# uMotion_v1_0.net
KiCad netlist of a schematic drawn in EAGLE
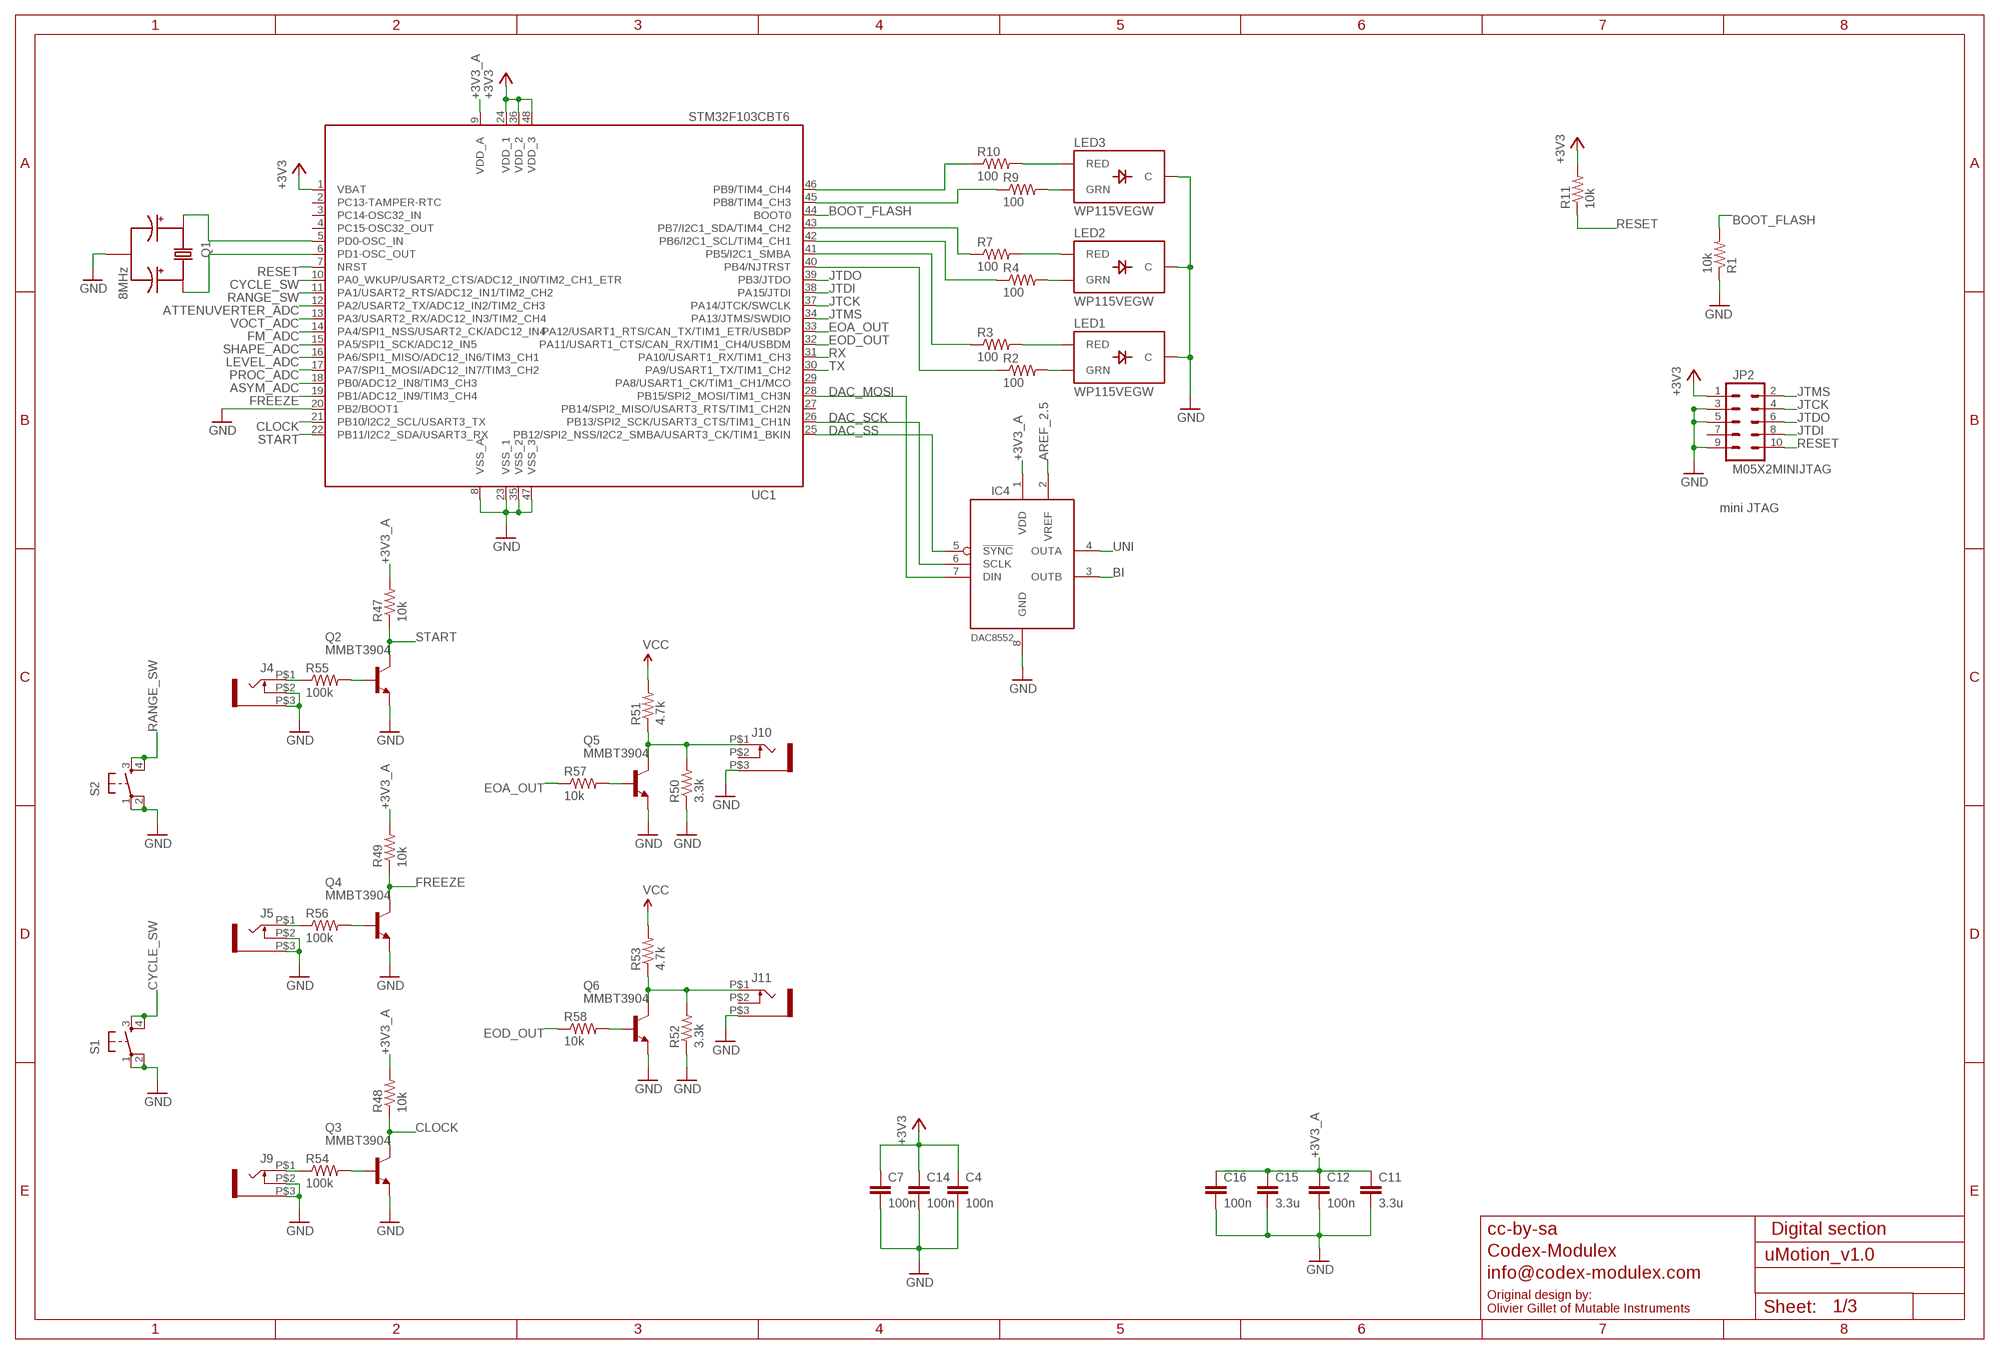
[diagram p0: schematic, sheet 1]
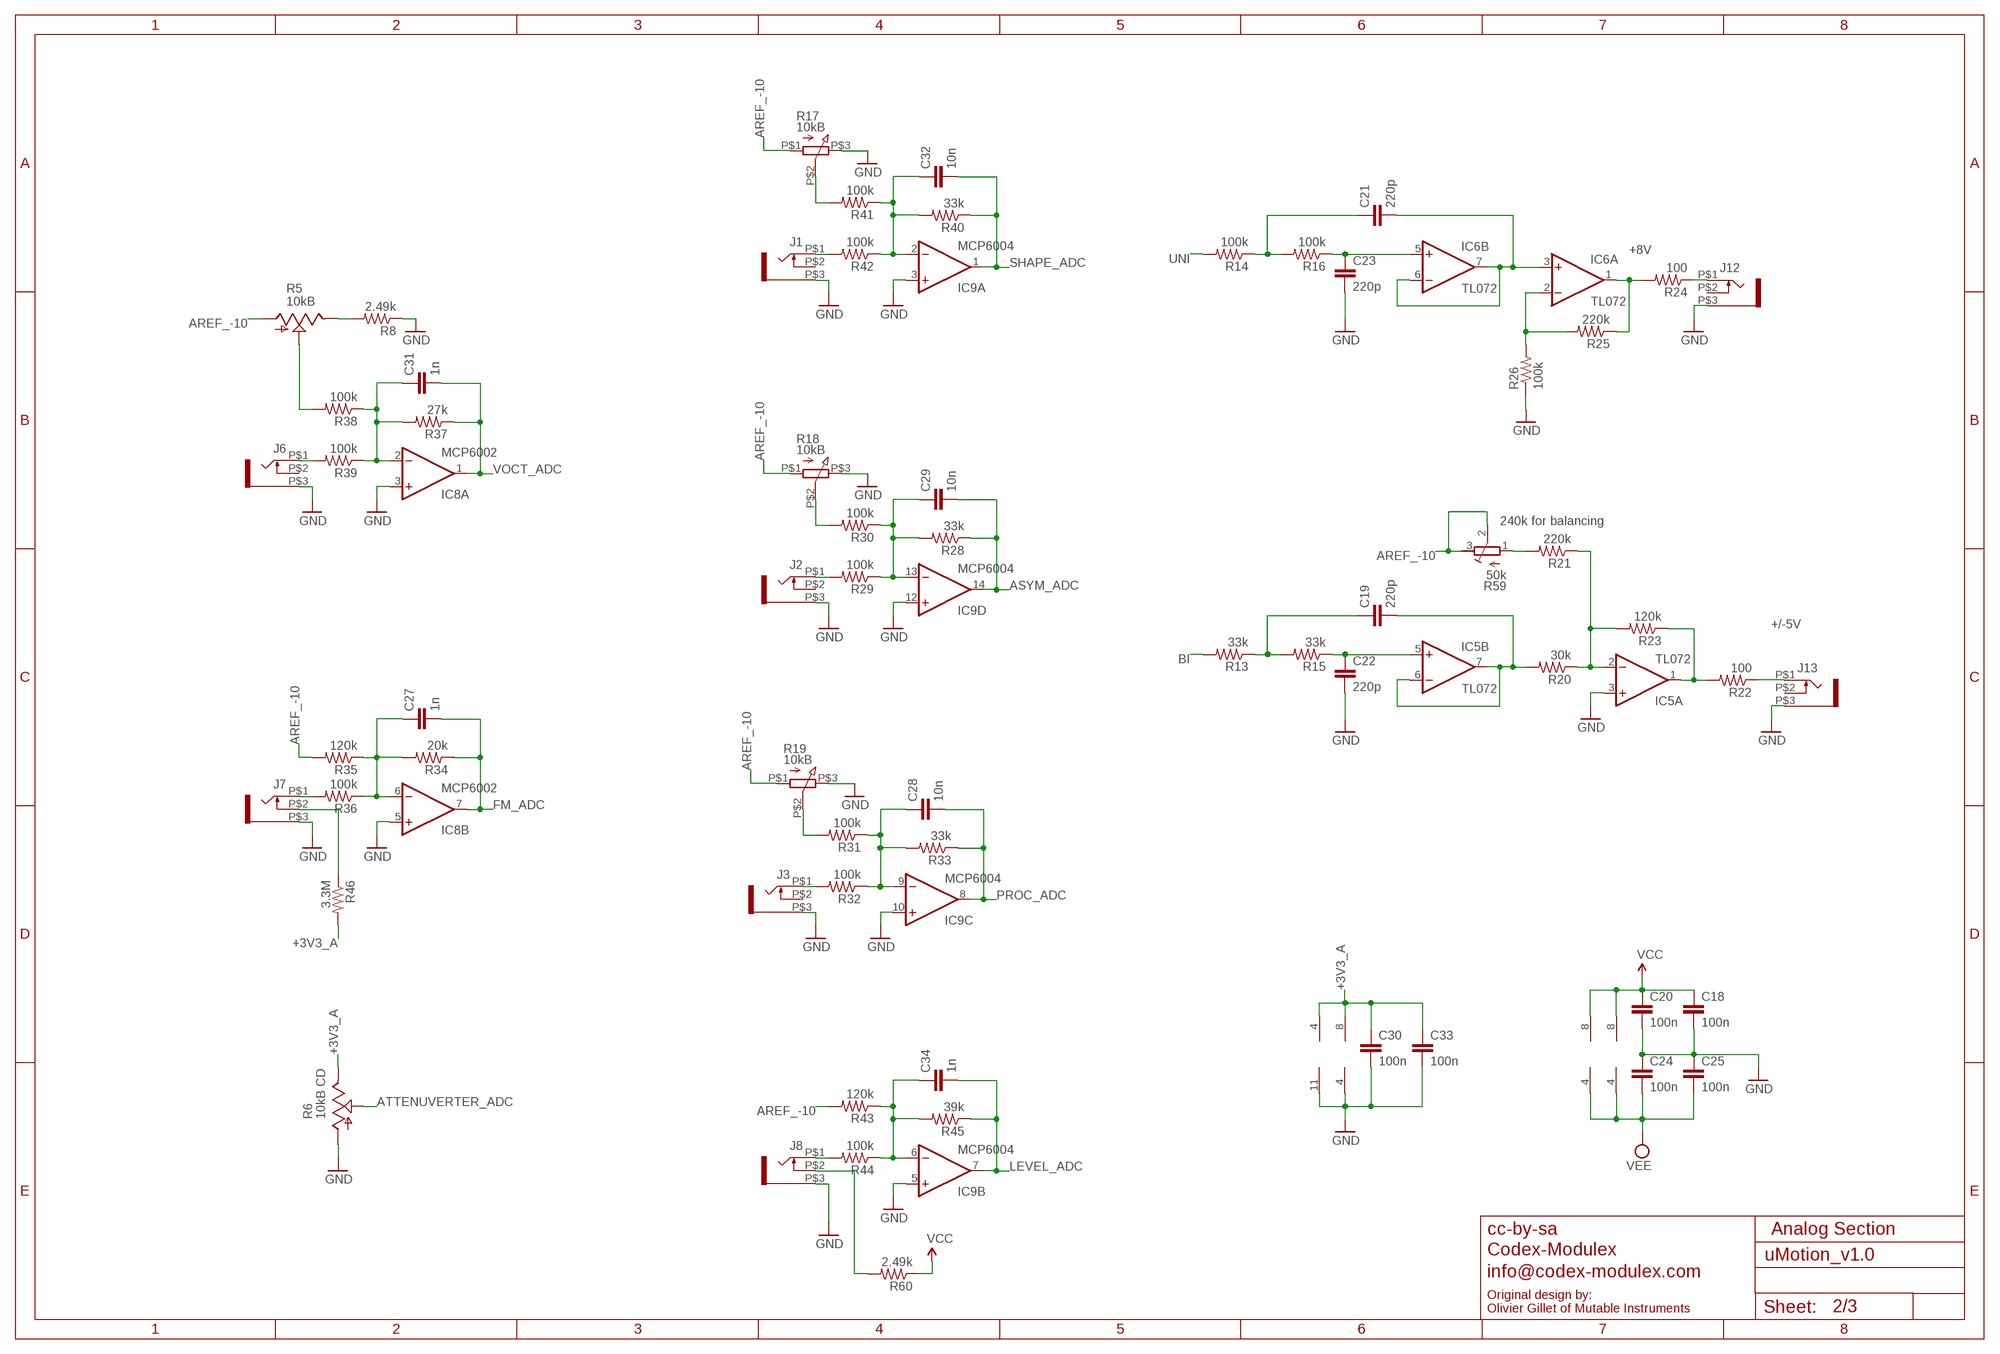
[diagram p1: schematic, sheet 2]
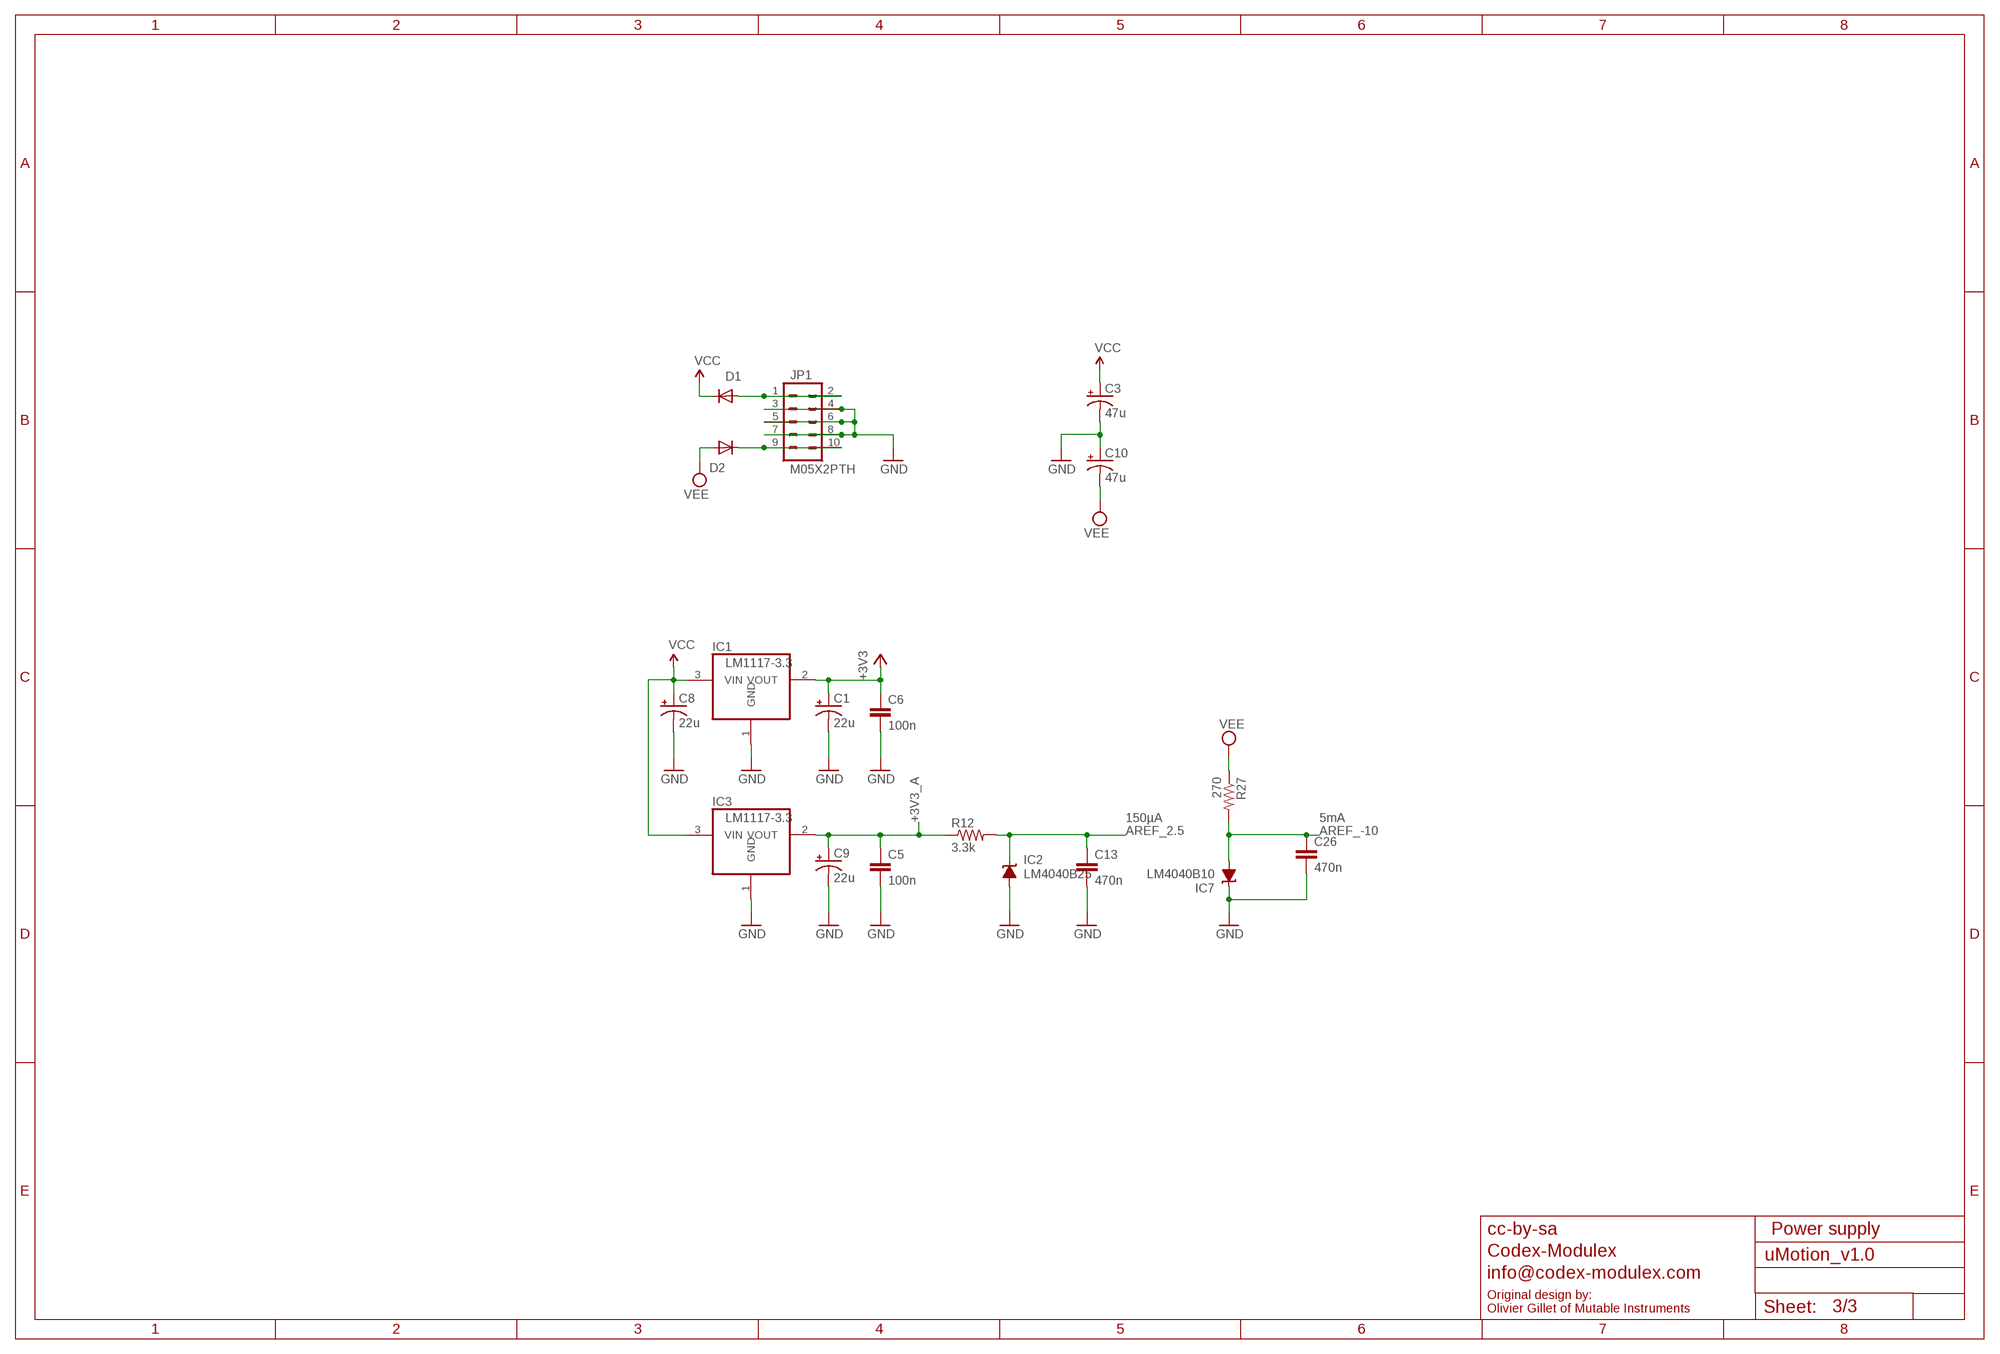
[diagram p2: schematic, sheet 3]

(export (version "E")
  (design (tool "Eeschema 10.0.6"))
  (components
    (comp (ref "C1")
      (value "22u")
      (footprint "eagle-import:PANASONIC_C")
      (libsource (lib "eagle-import") (part "CPOL-USC"))
    )
    (comp (ref "C3")
      (value "47u")
      (footprint "eagle-import:PANASONIC_D")
      (libsource (lib "eagle-import") (part "CPOL-USD"))
    )
    (comp (ref "C5")
      (value "100n")
      (footprint "eagle-import:PARTS_AMAN_RESISTOR_0603")
      (libsource (lib "eagle-import") (part "PARTS_AMAN_CAPACITOR"))
    )
    (comp (ref "C6")
      (value "100n")
      (footprint "eagle-import:PARTS_AMAN_RESISTOR_0603")
      (libsource (lib "eagle-import") (part "PARTS_AMAN_CAPACITOR"))
    )
    (comp (ref "C8")
      (value "22u")
      (footprint "eagle-import:PANASONIC_C")
      (libsource (lib "eagle-import") (part "CPOL-USC"))
    )
    (comp (ref "C9")
      (value "22u")
      (footprint "eagle-import:PANASONIC_C")
      (libsource (lib "eagle-import") (part "CPOL-USC"))
    )
    (comp (ref "C10")
      (value "47u")
      (footprint "eagle-import:PANASONIC_D")
      (libsource (lib "eagle-import") (part "CPOL-USD"))
    )
    (comp (ref "C13")
      (value "470n")
      (footprint "eagle-import:PARTS_AMAN_RESISTOR_0603")
      (libsource (lib "eagle-import") (part "PARTS_AMAN_CAPACITOR"))
    )
    (comp (ref "C26")
      (value "470n")
      (footprint "eagle-import:PARTS_AMAN_RESISTOR_0603")
      (libsource (lib "eagle-import") (part "PARTS_AMAN_CAPACITOR"))
    )
    (comp (ref "D1")
      (value "1N5819HW")
      (footprint "eagle-import:SOD123")
      (libsource (lib "eagle-import") (part "DIODE-SOD123"))
    )
    (comp (ref "D2")
      (value "1N5819HW")
      (footprint "eagle-import:SOD123")
      (libsource (lib "eagle-import") (part "DIODE-SOD123"))
    )
    (comp (ref "IC1")
      (value "LM1117-3.3")
      (footprint "eagle-import:SOT223")
      (libsource (lib "eagle-import") (part "REG1117"))
    )
    (comp (ref "IC2")
      (value "LM4040B25")
      (footprint "eagle-import:DBZ_R-PDSO-G3")
      (libsource (lib "eagle-import") (part "LM4041DBZB12"))
    )
    (comp (ref "IC3")
      (value "LM1117-3.3")
      (footprint "eagle-import:SOT223")
      (libsource (lib "eagle-import") (part "REG1117"))
    )
    (comp (ref "IC7")
      (value "LM4040B10")
      (footprint "eagle-import:DBZ_R-PDSO-G3")
      (libsource (lib "eagle-import") (part "LM4041DBZB12"))
    )
    (comp (ref "JP1")
      (value "M05X2PTH")
      (footprint "eagle-import:AVR_ICSP")
      (libsource (lib "eagle-import") (part "M05X2PTH"))
    )
    (comp (ref "R12")
      (value "3.3k")
      (footprint "eagle-import:PARTS_AMAN_RESISTOR_0603")
      (libsource (lib "eagle-import") (part "PARTS_AMAN_RESISTOR"))
    )
    (comp (ref "R27")
      (value "270")
      (footprint "eagle-import:PARTS_AMAN_RESISTOR_0603")
      (libsource (lib "eagle-import") (part "PARTS_AMAN_RESISTOR"))
    )
    (comp (ref "C18")
      (value "100n")
      (footprint "eagle-import:PARTS_AMAN_RESISTOR_0603")
      (libsource (lib "eagle-import") (part "PARTS_AMAN_CAPACITOR"))
    )
    (comp (ref "C19")
      (value "220p")
      (footprint "eagle-import:PARTS_AMAN_RESISTOR_0603")
      (libsource (lib "eagle-import") (part "PARTS_AMAN_CAPACITOR"))
    )
    (comp (ref "C20")
      (value "100n")
      (footprint "eagle-import:PARTS_AMAN_RESISTOR_0603")
      (libsource (lib "eagle-import") (part "PARTS_AMAN_CAPACITOR"))
    )
    (comp (ref "C21")
      (value "220p")
      (footprint "eagle-import:PARTS_AMAN_RESISTOR_0603")
      (libsource (lib "eagle-import") (part "PARTS_AMAN_CAPACITOR"))
    )
    (comp (ref "C22")
      (value "220p")
      (footprint "eagle-import:PARTS_AMAN_RESISTOR_0603")
      (libsource (lib "eagle-import") (part "PARTS_AMAN_CAPACITOR"))
    )
    (comp (ref "C23")
      (value "220p")
      (footprint "eagle-import:PARTS_AMAN_RESISTOR_0603")
      (libsource (lib "eagle-import") (part "PARTS_AMAN_CAPACITOR"))
    )
    (comp (ref "C24")
      (value "100n")
      (footprint "eagle-import:PARTS_AMAN_RESISTOR_0603")
      (libsource (lib "eagle-import") (part "PARTS_AMAN_CAPACITOR"))
    )
    (comp (ref "C25")
      (value "100n")
      (footprint "eagle-import:PARTS_AMAN_RESISTOR_0603")
      (libsource (lib "eagle-import") (part "PARTS_AMAN_CAPACITOR"))
    )
    (comp (ref "C27")
      (value "1n")
      (footprint "eagle-import:PARTS_AMAN_RESISTOR_0603")
      (libsource (lib "eagle-import") (part "PARTS_AMAN_CAPACITOR"))
    )
    (comp (ref "C28")
      (value "10n")
      (footprint "eagle-import:PARTS_AMAN_RESISTOR_0603")
      (libsource (lib "eagle-import") (part "PARTS_AMAN_CAPACITOR"))
    )
    (comp (ref "C29")
      (value "10n")
      (footprint "eagle-import:PARTS_AMAN_RESISTOR_0603")
      (libsource (lib "eagle-import") (part "PARTS_AMAN_CAPACITOR"))
    )
    (comp (ref "C30")
      (value "100n")
      (footprint "eagle-import:PARTS_AMAN_RESISTOR_0603")
      (libsource (lib "eagle-import") (part "PARTS_AMAN_CAPACITOR"))
    )
    (comp (ref "C31")
      (value "1n")
      (footprint "eagle-import:PARTS_AMAN_RESISTOR_0603")
      (libsource (lib "eagle-import") (part "PARTS_AMAN_CAPACITOR"))
    )
    (comp (ref "C32")
      (value "10n")
      (footprint "eagle-import:PARTS_AMAN_RESISTOR_0603")
      (libsource (lib "eagle-import") (part "PARTS_AMAN_CAPACITOR"))
    )
    (comp (ref "C33")
      (value "100n")
      (footprint "eagle-import:PARTS_AMAN_RESISTOR_0603")
      (libsource (lib "eagle-import") (part "PARTS_AMAN_CAPACITOR"))
    )
    (comp (ref "C34")
      (value "1n")
      (footprint "eagle-import:PARTS_AMAN_RESISTOR_0603")
      (libsource (lib "eagle-import") (part "PARTS_AMAN_CAPACITOR"))
    )
    (comp (ref "IC5")
      (value "TL072")
      (footprint "eagle-import:SO08")
      (libsource (lib "eagle-import") (part "TL072D"))
    )
    (comp (ref "IC6")
      (value "TL072")
      (footprint "eagle-import:SO08")
      (libsource (lib "eagle-import") (part "TL072D"))
    )
    (comp (ref "IC8")
      (value "MCP6002")
      (footprint "eagle-import:SO08")
      (libsource (lib "eagle-import") (part "TL072D"))
    )
    (comp (ref "IC9")
      (value "MCP6004")
      (footprint "eagle-import:SO14")
      (libsource (lib "eagle-import") (part "TL074D"))
    )
    (comp (ref "J1")
      (value "WQP-PJ301M-12_JACK")
      (footprint "eagle-import:WQP-PJ301M-12_JACK")
      (libsource (lib "eagle-import") (part "WQP-PJ301M-12_JACK"))
    )
    (comp (ref "J2")
      (value "WQP-PJ301M-12_JACK")
      (footprint "eagle-import:WQP-PJ301M-12_JACK")
      (libsource (lib "eagle-import") (part "WQP-PJ301M-12_JACK"))
    )
    (comp (ref "J3")
      (value "WQP-PJ301M-12_JACK")
      (footprint "eagle-import:WQP-PJ301M-12_JACK")
      (libsource (lib "eagle-import") (part "WQP-PJ301M-12_JACK"))
    )
    (comp (ref "J6")
      (value "WQP-PJ301M-12_JACK")
      (footprint "eagle-import:WQP-PJ301M-12_JACK")
      (libsource (lib "eagle-import") (part "WQP-PJ301M-12_JACK"))
    )
    (comp (ref "J7")
      (value "WQP-PJ301M-12_JACK")
      (footprint "eagle-import:WQP-PJ301M-12_JACK")
      (libsource (lib "eagle-import") (part "WQP-PJ301M-12_JACK"))
    )
    (comp (ref "J8")
      (value "WQP-PJ301M-12_JACK")
      (footprint "eagle-import:WQP-PJ301M-12_JACK")
      (libsource (lib "eagle-import") (part "WQP-PJ301M-12_JACK"))
    )
    (comp (ref "J12")
      (value "WQP-PJ301M-12_JACK")
      (footprint "eagle-import:WQP-PJ301M-12_JACK")
      (libsource (lib "eagle-import") (part "WQP-PJ301M-12_JACK"))
    )
    (comp (ref "J13")
      (value "WQP-PJ301M-12_JACK")
      (footprint "eagle-import:WQP-PJ301M-12_JACK")
      (libsource (lib "eagle-import") (part "WQP-PJ301M-12_JACK"))
    )
    (comp (ref "R5")
      (value "10kB")
      (footprint "eagle-import:ALPS_POT_VERTICAL_PS")
      (libsource (lib "eagle-import") (part "POT_USVERTICAL_PS"))
    )
    (comp (ref "R6")
      (value "10kB CD")
      (footprint "eagle-import:ALPS_POT_VERTICAL_PS")
      (libsource (lib "eagle-import") (part "POT_USVERTICAL_PS"))
    )
    (comp (ref "R8")
      (value "2.49k")
      (footprint "eagle-import:PARTS_AMAN_RESISTOR_0603")
      (libsource (lib "eagle-import") (part "PARTS_AMAN_RESISTOR"))
    )
    (comp (ref "R13")
      (value "33k")
      (footprint "eagle-import:PARTS_AMAN_RESISTOR_0603")
      (libsource (lib "eagle-import") (part "PARTS_AMAN_RESISTOR"))
    )
    (comp (ref "R14")
      (value "100k")
      (footprint "eagle-import:PARTS_AMAN_RESISTOR_0603")
      (libsource (lib "eagle-import") (part "PARTS_AMAN_RESISTOR"))
    )
    (comp (ref "R15")
      (value "33k")
      (footprint "eagle-import:PARTS_AMAN_RESISTOR_0603")
      (libsource (lib "eagle-import") (part "PARTS_AMAN_RESISTOR"))
    )
    (comp (ref "R16")
      (value "100k")
      (footprint "eagle-import:PARTS_AMAN_RESISTOR_0603")
      (libsource (lib "eagle-import") (part "PARTS_AMAN_RESISTOR"))
    )
    (comp (ref "R17")
      (value "10kB")
      (footprint "eagle-import:INSTRUO_Q-POT2")
      (libsource (lib "eagle-import") (part "INSTRUO_Q-POT2"))
    )
    (comp (ref "R18")
      (value "10kB")
      (footprint "eagle-import:INSTRUO_Q-POT2")
      (libsource (lib "eagle-import") (part "INSTRUO_Q-POT2"))
    )
    (comp (ref "R19")
      (value "10kB")
      (footprint "eagle-import:INSTRUO_Q-POT2")
      (libsource (lib "eagle-import") (part "INSTRUO_Q-POT2"))
    )
    (comp (ref "R20")
      (value "30k")
      (footprint "eagle-import:PARTS_AMAN_RESISTOR_0603")
      (libsource (lib "eagle-import") (part "PARTS_AMAN_RESISTOR"))
    )
    (comp (ref "R21")
      (value "220k")
      (footprint "eagle-import:PARTS_AMAN_RESISTOR_0603")
      (libsource (lib "eagle-import") (part "PARTS_AMAN_RESISTOR"))
    )
    (comp (ref "R22")
      (value "100")
      (footprint "eagle-import:PARTS_AMAN_RESISTOR_0603")
      (libsource (lib "eagle-import") (part "PARTS_AMAN_RESISTOR"))
    )
    (comp (ref "R23")
      (value "120k")
      (footprint "eagle-import:PARTS_AMAN_RESISTOR_0603")
      (libsource (lib "eagle-import") (part "PARTS_AMAN_RESISTOR"))
    )
    (comp (ref "R24")
      (value "100")
      (footprint "eagle-import:PARTS_AMAN_RESISTOR_0603")
      (libsource (lib "eagle-import") (part "PARTS_AMAN_RESISTOR"))
    )
    (comp (ref "R25")
      (value "220k")
      (footprint "eagle-import:PARTS_AMAN_RESISTOR_0603")
      (libsource (lib "eagle-import") (part "PARTS_AMAN_RESISTOR"))
    )
    (comp (ref "R26")
      (value "100k")
      (footprint "eagle-import:PARTS_AMAN_RESISTOR_0603")
      (libsource (lib "eagle-import") (part "PARTS_AMAN_RESISTOR"))
    )
    (comp (ref "R28")
      (value "33k")
      (footprint "eagle-import:PARTS_AMAN_RESISTOR_0603")
      (libsource (lib "eagle-import") (part "PARTS_AMAN_RESISTOR"))
    )
    (comp (ref "R29")
      (value "100k")
      (footprint "eagle-import:PARTS_AMAN_RESISTOR_0603")
      (libsource (lib "eagle-import") (part "PARTS_AMAN_RESISTOR"))
    )
    (comp (ref "R30")
      (value "100k")
      (footprint "eagle-import:PARTS_AMAN_RESISTOR_0603")
      (libsource (lib "eagle-import") (part "PARTS_AMAN_RESISTOR"))
    )
    (comp (ref "R31")
      (value "100k")
      (footprint "eagle-import:PARTS_AMAN_RESISTOR_0603")
      (libsource (lib "eagle-import") (part "PARTS_AMAN_RESISTOR"))
    )
    (comp (ref "R32")
      (value "100k")
      (footprint "eagle-import:PARTS_AMAN_RESISTOR_0603")
      (libsource (lib "eagle-import") (part "PARTS_AMAN_RESISTOR"))
    )
    (comp (ref "R33")
      (value "33k")
      (footprint "eagle-import:PARTS_AMAN_RESISTOR_0603")
      (libsource (lib "eagle-import") (part "PARTS_AMAN_RESISTOR"))
    )
    (comp (ref "R34")
      (value "20k")
      (footprint "eagle-import:PARTS_AMAN_RESISTOR_0603")
      (libsource (lib "eagle-import") (part "PARTS_AMAN_RESISTOR"))
    )
    (comp (ref "R35")
      (value "120k")
      (footprint "eagle-import:PARTS_AMAN_RESISTOR_0603")
      (libsource (lib "eagle-import") (part "PARTS_AMAN_RESISTOR"))
    )
    (comp (ref "R36")
      (value "100k")
      (footprint "eagle-import:PARTS_AMAN_RESISTOR_0603")
      (libsource (lib "eagle-import") (part "PARTS_AMAN_RESISTOR"))
    )
    (comp (ref "R37")
      (value "27k")
      (footprint "eagle-import:PARTS_AMAN_RESISTOR_0603")
      (libsource (lib "eagle-import") (part "PARTS_AMAN_RESISTOR"))
    )
    (comp (ref "R38")
      (value "100k")
      (footprint "eagle-import:PARTS_AMAN_RESISTOR_0603")
      (libsource (lib "eagle-import") (part "PARTS_AMAN_RESISTOR"))
    )
    (comp (ref "R39")
      (value "100k")
      (footprint "eagle-import:PARTS_AMAN_RESISTOR_0603")
      (libsource (lib "eagle-import") (part "PARTS_AMAN_RESISTOR"))
    )
    (comp (ref "R40")
      (value "33k")
      (footprint "eagle-import:PARTS_AMAN_RESISTOR_0603")
      (libsource (lib "eagle-import") (part "PARTS_AMAN_RESISTOR"))
    )
    (comp (ref "R41")
      (value "100k")
      (footprint "eagle-import:PARTS_AMAN_RESISTOR_0603")
      (libsource (lib "eagle-import") (part "PARTS_AMAN_RESISTOR"))
    )
    (comp (ref "R42")
      (value "100k")
      (footprint "eagle-import:PARTS_AMAN_RESISTOR_0603")
      (libsource (lib "eagle-import") (part "PARTS_AMAN_RESISTOR"))
    )
    (comp (ref "R43")
      (value "120k")
      (footprint "eagle-import:PARTS_AMAN_RESISTOR_0603")
      (libsource (lib "eagle-import") (part "PARTS_AMAN_RESISTOR"))
    )
    (comp (ref "R44")
      (value "100k")
      (footprint "eagle-import:PARTS_AMAN_RESISTOR_0603")
      (libsource (lib "eagle-import") (part "PARTS_AMAN_RESISTOR"))
    )
    (comp (ref "R45")
      (value "39k")
      (footprint "eagle-import:PARTS_AMAN_RESISTOR_0603")
      (libsource (lib "eagle-import") (part "PARTS_AMAN_RESISTOR"))
    )
    (comp (ref "R46")
      (value "3.3M")
      (footprint "eagle-import:PARTS_AMAN_RESISTOR_0603")
      (libsource (lib "eagle-import") (part "PARTS_AMAN_RESISTOR"))
    )
    (comp (ref "R59")
      (value "50k")
      (footprint "eagle-import:RTRIM3296X")
      (libsource (lib "eagle-import") (part "R-TRIMM3296X"))
    )
    (comp (ref "R60")
      (value "2.49k")
      (footprint "eagle-import:R0805")
      (libsource (lib "eagle-import") (part "R-US_R0805"))
    )
    (comp (ref "C4")
      (value "100n")
      (footprint "eagle-import:PARTS_AMAN_RESISTOR_0603")
      (libsource (lib "eagle-import") (part "PARTS_AMAN_CAPACITOR"))
    )
    (comp (ref "C7")
      (value "100n")
      (footprint "eagle-import:PARTS_AMAN_RESISTOR_0603")
      (libsource (lib "eagle-import") (part "PARTS_AMAN_CAPACITOR"))
    )
    (comp (ref "C11")
      (value "3.3u")
      (footprint "eagle-import:PARTS_AMAN_RESISTOR_0603")
      (libsource (lib "eagle-import") (part "PARTS_AMAN_CAPACITOR"))
    )
    (comp (ref "C12")
      (value "100n")
      (footprint "eagle-import:PARTS_AMAN_RESISTOR_0603")
      (libsource (lib "eagle-import") (part "PARTS_AMAN_CAPACITOR"))
    )
    (comp (ref "C14")
      (value "100n")
      (footprint "eagle-import:PARTS_AMAN_RESISTOR_0603")
      (libsource (lib "eagle-import") (part "PARTS_AMAN_CAPACITOR"))
    )
    (comp (ref "C15")
      (value "3.3u")
      (footprint "eagle-import:PARTS_AMAN_RESISTOR_0603")
      (libsource (lib "eagle-import") (part "PARTS_AMAN_CAPACITOR"))
    )
    (comp (ref "C16")
      (value "100n")
      (footprint "eagle-import:PARTS_AMAN_RESISTOR_0603")
      (libsource (lib "eagle-import") (part "PARTS_AMAN_CAPACITOR"))
    )
    (comp (ref "IC4")
      (value "DAC8552")
      (footprint "eagle-import:MSOP-8")
      (libsource (lib "eagle-import") (part "DAC8552"))
    )
    (comp (ref "J4")
      (value "WQP-PJ301M-12_JACK")
      (footprint "eagle-import:WQP-PJ301M-12_JACK")
      (libsource (lib "eagle-import") (part "WQP-PJ301M-12_JACK"))
    )
    (comp (ref "J5")
      (value "WQP-PJ301M-12_JACK")
      (footprint "eagle-import:WQP-PJ301M-12_JACK")
      (libsource (lib "eagle-import") (part "WQP-PJ301M-12_JACK"))
    )
    (comp (ref "J9")
      (value "WQP-PJ301M-12_JACK")
      (footprint "eagle-import:WQP-PJ301M-12_JACK")
      (libsource (lib "eagle-import") (part "WQP-PJ301M-12_JACK"))
    )
    (comp (ref "J10")
      (value "WQP-PJ301M-12_JACK")
      (footprint "eagle-import:WQP-PJ301M-12_JACK")
      (libsource (lib "eagle-import") (part "WQP-PJ301M-12_JACK"))
    )
    (comp (ref "J11")
      (value "WQP-PJ301M-12_JACK")
      (footprint "eagle-import:WQP-PJ301M-12_JACK")
      (libsource (lib "eagle-import") (part "WQP-PJ301M-12_JACK"))
    )
    (comp (ref "JP2")
      (value "M05X2MINIJTAG")
      (footprint "eagle-import:2X5-1.27")
      (libsource (lib "eagle-import") (part "M05X2MINIJTAG"))
    )
    (comp (ref "LED1")
      (value "WP115VEGW")
      (footprint "eagle-import:LED-BICOLOR-THROUGHHOLE")
      (libsource (lib "eagle-import") (part "LED-BICOLOR-THROUGHHOLE"))
    )
    (comp (ref "LED2")
      (value "WP115VEGW")
      (footprint "eagle-import:LED-BICOLOR-THROUGHHOLE")
      (libsource (lib "eagle-import") (part "LED-BICOLOR-THROUGHHOLE"))
    )
    (comp (ref "LED3")
      (value "WP115VEGW")
      (footprint "eagle-import:LED-BICOLOR-THROUGHHOLE")
      (libsource (lib "eagle-import") (part "LED-BICOLOR-THROUGHHOLE"))
    )
    (comp (ref "Q1")
      (value "8MHz")
      (footprint "eagle-import:INSTRUO_CRYSTAL_SMALLER")
      (libsource (lib "eagle-import") (part "INSTRUO_CRYSTAL_SMALLER"))
    )
    (comp (ref "Q2")
      (value "MMBT3904")
      (footprint "eagle-import:SOT23-BEC")
      (libsource (lib "eagle-import") (part "-NPN-SOT23-BECMMBT3904LT1"))
    )
    (comp (ref "Q3")
      (value "MMBT3904")
      (footprint "eagle-import:SOT23-BEC")
      (libsource (lib "eagle-import") (part "-NPN-SOT23-BECMMBT3904LT1"))
    )
    (comp (ref "Q4")
      (value "MMBT3904")
      (footprint "eagle-import:SOT23-BEC")
      (libsource (lib "eagle-import") (part "-NPN-SOT23-BECMMBT3904LT1"))
    )
    (comp (ref "Q5")
      (value "MMBT3904")
      (footprint "eagle-import:SOT23-BEC")
      (libsource (lib "eagle-import") (part "-NPN-SOT23-BECMMBT3904LT1"))
    )
    (comp (ref "Q6")
      (value "MMBT3904")
      (footprint "eagle-import:SOT23-BEC")
      (libsource (lib "eagle-import") (part "-NPN-SOT23-BECMMBT3904LT1"))
    )
    (comp (ref "R1")
      (value "10k")
      (footprint "eagle-import:PARTS_AMAN_RESISTOR_0603")
      (libsource (lib "eagle-import") (part "PARTS_AMAN_RESISTOR"))
    )
    (comp (ref "R2")
      (value "100")
      (footprint "eagle-import:PARTS_AMAN_RESISTOR_0603")
      (libsource (lib "eagle-import") (part "PARTS_AMAN_RESISTOR"))
    )
    (comp (ref "R3")
      (value "100")
      (footprint "eagle-import:PARTS_AMAN_RESISTOR_0603")
      (libsource (lib "eagle-import") (part "PARTS_AMAN_RESISTOR"))
    )
    (comp (ref "R4")
      (value "100")
      (footprint "eagle-import:PARTS_AMAN_RESISTOR_0603")
      (libsource (lib "eagle-import") (part "PARTS_AMAN_RESISTOR"))
    )
    (comp (ref "R7")
      (value "100")
      (footprint "eagle-import:PARTS_AMAN_RESISTOR_0603")
      (libsource (lib "eagle-import") (part "PARTS_AMAN_RESISTOR"))
    )
    (comp (ref "R9")
      (value "100")
      (footprint "eagle-import:PARTS_AMAN_RESISTOR_0603")
      (libsource (lib "eagle-import") (part "PARTS_AMAN_RESISTOR"))
    )
    (comp (ref "R10")
      (value "100")
      (footprint "eagle-import:PARTS_AMAN_RESISTOR_0603")
      (libsource (lib "eagle-import") (part "PARTS_AMAN_RESISTOR"))
    )
    (comp (ref "R11")
      (value "10k")
      (footprint "eagle-import:PARTS_AMAN_RESISTOR_0603")
      (libsource (lib "eagle-import") (part "PARTS_AMAN_RESISTOR"))
    )
    (comp (ref "R47")
      (value "10k")
      (footprint "eagle-import:PARTS_AMAN_RESISTOR_0603")
      (libsource (lib "eagle-import") (part "PARTS_AMAN_RESISTOR"))
    )
    (comp (ref "R48")
      (value "10k")
      (footprint "eagle-import:PARTS_AMAN_RESISTOR_0603")
      (libsource (lib "eagle-import") (part "PARTS_AMAN_RESISTOR"))
    )
    (comp (ref "R49")
      (value "10k")
      (footprint "eagle-import:PARTS_AMAN_RESISTOR_0603")
      (libsource (lib "eagle-import") (part "PARTS_AMAN_RESISTOR"))
    )
    (comp (ref "R50")
      (value "3.3k")
      (footprint "eagle-import:PARTS_AMAN_RESISTOR_0603")
      (libsource (lib "eagle-import") (part "PARTS_AMAN_RESISTOR"))
    )
    (comp (ref "R51")
      (value "4.7k")
      (footprint "eagle-import:PARTS_AMAN_RESISTOR_0603")
      (libsource (lib "eagle-import") (part "PARTS_AMAN_RESISTOR"))
    )
    (comp (ref "R52")
      (value "3.3k")
      (footprint "eagle-import:PARTS_AMAN_RESISTOR_0603")
      (libsource (lib "eagle-import") (part "PARTS_AMAN_RESISTOR"))
    )
    (comp (ref "R53")
      (value "4.7k")
      (footprint "eagle-import:PARTS_AMAN_RESISTOR_0603")
      (libsource (lib "eagle-import") (part "PARTS_AMAN_RESISTOR"))
    )
    (comp (ref "R54")
      (value "100k")
      (footprint "eagle-import:PARTS_AMAN_RESISTOR_0603")
      (libsource (lib "eagle-import") (part "PARTS_AMAN_RESISTOR"))
    )
    (comp (ref "R55")
      (value "100k")
      (footprint "eagle-import:PARTS_AMAN_RESISTOR_0603")
      (libsource (lib "eagle-import") (part "PARTS_AMAN_RESISTOR"))
    )
    (comp (ref "R56")
      (value "100k")
      (footprint "eagle-import:PARTS_AMAN_RESISTOR_0603")
      (libsource (lib "eagle-import") (part "PARTS_AMAN_RESISTOR"))
    )
    (comp (ref "R57")
      (value "10k")
      (footprint "eagle-import:PARTS_AMAN_RESISTOR_0603")
      (libsource (lib "eagle-import") (part "PARTS_AMAN_RESISTOR"))
    )
    (comp (ref "R58")
      (value "10k")
      (footprint "eagle-import:PARTS_AMAN_RESISTOR_0603")
      (libsource (lib "eagle-import") (part "PARTS_AMAN_RESISTOR"))
    )
    (comp (ref "S1")
      (value "TAC_SWITCHPTH")
      (footprint "eagle-import:TACTILE-PTH")
      (libsource (lib "eagle-import") (part "TAC_SWITCHPTH"))
    )
    (comp (ref "S2")
      (value "TAC_SWITCHPTH")
      (footprint "eagle-import:TACTILE-PTH")
      (libsource (lib "eagle-import") (part "TAC_SWITCHPTH"))
    )
    (comp (ref "UC1")
      (value "STM32F103CBT6")
      (footprint "eagle-import:LQFP48")
      (libsource (lib "eagle-import") (part "STM32F103CB"))
    )
  )
  (nets
    (net (code "1") (name "+3V3") (class "Default")
      (node (ref "C1") (pin "+") (pinfunction "+_+") (pintype "passive"))
      (node (ref "C14") (pin "1") (pinfunction "1_1") (pintype "passive"))
      (node (ref "C4") (pin "1") (pinfunction "1_1") (pintype "passive"))
      (node (ref "C6") (pin "1") (pinfunction "1_1") (pintype "passive"))
      (node (ref "C7") (pin "1") (pinfunction "1_1") (pintype "passive"))
      (node (ref "IC1") (pin "2") (pinfunction "VOUT_2") (pintype "output"))
      (node (ref "JP2") (pin "1") (pinfunction "1_1") (pintype "passive"))
      (node (ref "R11") (pin "2") (pinfunction "2_2") (pintype "passive"))
      (node (ref "UC1") (pin "1") (pinfunction "VBAT_1") (pintype "power_in"))
      (node (ref "UC1") (pin "24") (pinfunction "VDD_1_24") (pintype "power_in"))
      (node (ref "UC1") (pin "36") (pinfunction "VDD_2_36") (pintype "power_in"))
      (node (ref "UC1") (pin "48") (pinfunction "VDD_3_48") (pintype "power_in"))
    )
    (net (code "2") (name "+3V3_A") (class "Default")
      (node (ref "C11") (pin "1") (pinfunction "1_1") (pintype "passive"))
      (node (ref "C12") (pin "1") (pinfunction "1_1") (pintype "passive"))
      (node (ref "C15") (pin "1") (pinfunction "1_1") (pintype "passive"))
      (node (ref "C16") (pin "1") (pinfunction "1_1") (pintype "passive"))
      (node (ref "C30") (pin "1") (pinfunction "1_1") (pintype "passive"))
      (node (ref "C33") (pin "1") (pinfunction "1_1") (pintype "passive"))
      (node (ref "C5") (pin "1") (pinfunction "1_1") (pintype "passive"))
      (node (ref "C9") (pin "+") (pinfunction "+_+") (pintype "passive"))
      (node (ref "IC3") (pin "2") (pinfunction "VOUT_2") (pintype "output"))
      (node (ref "IC4") (pin "1") (pinfunction "VDD_1") (pintype "power_in"))
      (node (ref "IC8") (pin "8") (pinfunction "V+_8") (pintype "power_in"))
      (node (ref "IC9") (pin "4") (pinfunction "V+_4") (pintype "power_in"))
      (node (ref "R12") (pin "1") (pinfunction "1_1") (pintype "passive"))
      (node (ref "R46") (pin "2") (pinfunction "2_2") (pintype "passive"))
      (node (ref "R47") (pin "2") (pinfunction "2_2") (pintype "passive"))
      (node (ref "R48") (pin "2") (pinfunction "2_2") (pintype "passive"))
      (node (ref "R49") (pin "2") (pinfunction "2_2") (pintype "passive"))
      (node (ref "R6") (pin "P$1") (pinfunction "E_P$1") (pintype "passive"))
      (node (ref "UC1") (pin "9") (pinfunction "VDD_A_9") (pintype "power_in"))
    )
    (net (code "3") (name "AREF_-10") (class "Default")
      (node (ref "C26") (pin "1") (pinfunction "1_1") (pintype "passive"))
      (node (ref "IC7") (pin "2") (pinfunction "A_2") (pintype "passive"))
      (node (ref "R17") (pin "P$1") (pinfunction "1_P$1") (pintype "passive"))
      (node (ref "R18") (pin "P$1") (pinfunction "1_P$1") (pintype "passive"))
      (node (ref "R19") (pin "P$1") (pinfunction "1_P$1") (pintype "passive"))
      (node (ref "R27") (pin "2") (pinfunction "2_2") (pintype "passive"))
      (node (ref "R35") (pin "2") (pinfunction "2_2") (pintype "passive"))
      (node (ref "R43") (pin "2") (pinfunction "2_2") (pintype "passive"))
      (node (ref "R5") (pin "P$3") (pinfunction "A_P$3") (pintype "passive"))
      (node (ref "R59") (pin "2") (pinfunction "S_2") (pintype "passive"))
      (node (ref "R59") (pin "3") (pinfunction "A_3") (pintype "passive"))
    )
    (net (code "4") (name "AREF_2.5") (class "Default")
      (node (ref "C13") (pin "1") (pinfunction "1_1") (pintype "passive"))
      (node (ref "IC2") (pin "1") (pinfunction "C_1") (pintype "passive"))
      (node (ref "IC4") (pin "2") (pinfunction "VREF_2") (pintype "power_in"))
      (node (ref "R12") (pin "2") (pinfunction "2_2") (pintype "passive"))
    )
    (net (code "5") (name "ASYM_ADC") (class "Default")
      (node (ref "C29") (pin "2") (pinfunction "2_2") (pintype "passive"))
      (node (ref "IC9") (pin "14") (pinfunction "OUT_14") (pintype "output"))
      (node (ref "R28") (pin "1") (pinfunction "1_1") (pintype "passive"))
      (node (ref "UC1") (pin "18") (pinfunction "PB0/ADC12_IN8/TIM3_CH3_18") (pintype "bidirectional"))
    )
    (net (code "6") (name "ATTENUVERTER_ADC") (class "Default")
      (node (ref "R6") (pin "P$2") (pinfunction "S_P$2") (pintype "passive"))
      (node (ref "UC1") (pin "12") (pinfunction "PA2/USART2_TX/ADC12_IN2/TIM2_CH3_12") (pintype "bidirectional"))
    )
    (net (code "7") (name "BI") (class "Default")
      (node (ref "IC4") (pin "3") (pinfunction "OUTB_3") (pintype "input"))
      (node (ref "R13") (pin "2") (pinfunction "2_2") (pintype "passive"))
    )
    (net (code "8") (name "BOOT_FLASH") (class "Default")
      (node (ref "R1") (pin "2") (pinfunction "2_2") (pintype "passive"))
      (node (ref "UC1") (pin "44") (pinfunction "BOOT0_44") (pintype "input"))
    )
    (net (code "9") (name "CLOCK") (class "Default")
      (node (ref "Q3") (pin "C") (pinfunction "C_C") (pintype "passive"))
      (node (ref "R48") (pin "1") (pinfunction "1_1") (pintype "passive"))
      (node (ref "UC1") (pin "21") (pinfunction "PB10/I2C2_SCL/USART3_TX_21") (pintype "input"))
    )
    (net (code "10") (name "CYCLE_SW") (class "Default")
      (node (ref "S1") (pin "3") (pinfunction "3_3") (pintype "passive"))
      (node (ref "S1") (pin "4") (pinfunction "4_4") (pintype "passive"))
      (node (ref "UC1") (pin "10") (pinfunction "PA0_WKUP/USART2_CTS/ADC12_IN0/TIM2_CH1_ETR_10") (pintype "bidirectional"))
    )
    (net (code "11") (name "DAC_MOSI") (class "Default")
      (node (ref "IC4") (pin "7") (pinfunction "DIN_7") (pintype "bidirectional"))
      (node (ref "UC1") (pin "28") (pinfunction "PB15/SPI2_MOSI/TIM1_CH3N_28") (pintype "input"))
    )
    (net (code "12") (name "DAC_SCK") (class "Default")
      (node (ref "IC4") (pin "6") (pinfunction "SCLK_6") (pintype "bidirectional"))
      (node (ref "UC1") (pin "26") (pinfunction "PB13/SPI2_SCK/USART3_CTS/TIM1_CH1N_26") (pintype "input"))
    )
    (net (code "13") (name "DAC_SS") (class "Default")
      (node (ref "IC4") (pin "5") (pinfunction "~{SYNC}_5") (pintype "bidirectional"))
      (node (ref "UC1") (pin "25") (pinfunction "PB12/SPI2_NSS/I2C2_SMBA/USART3_CK/TIM1_BKIN_25") (pintype "input"))
    )
    (net (code "14") (name "EOA_OUT") (class "Default")
      (node (ref "R57") (pin "1") (pinfunction "1_1") (pintype "passive"))
      (node (ref "UC1") (pin "33") (pinfunction "PA12/USART1_RTS/CAN_TX/TIM1_ETR/USBDP_33") (pintype "bidirectional"))
    )
    (net (code "15") (name "EOD_OUT") (class "Default")
      (node (ref "R58") (pin "1") (pinfunction "1_1") (pintype "passive"))
      (node (ref "UC1") (pin "32") (pinfunction "PA11/USART1_CTS/CAN_RX/TIM1_CH4/USBDM_32") (pintype "bidirectional"))
    )
    (net (code "16") (name "FM_ADC") (class "Default")
      (node (ref "C27") (pin "2") (pinfunction "2_2") (pintype "passive"))
      (node (ref "IC8") (pin "7") (pinfunction "OUT_7") (pintype "output"))
      (node (ref "R34") (pin "1") (pinfunction "1_1") (pintype "passive"))
      (node (ref "UC1") (pin "14") (pinfunction "PA4/SPI1_NSS/USART2_CK/ADC12_IN4_14") (pintype "bidirectional"))
    )
    (net (code "17") (name "FREEZE") (class "Default")
      (node (ref "Q4") (pin "C") (pinfunction "C_C") (pintype "passive"))
      (node (ref "R49") (pin "1") (pinfunction "1_1") (pintype "passive"))
      (node (ref "UC1") (pin "19") (pinfunction "PB1/ADC12_IN9/TIM3_CH4_19") (pintype "bidirectional"))
    )
    (net (code "18") (name "GND") (class "Default")
      (node (ref "C1") (pin "-") (pinfunction "-_-") (pintype "passive"))
      (node (ref "C10") (pin "+") (pinfunction "+_+") (pintype "passive"))
      (node (ref "C11") (pin "2") (pinfunction "2_2") (pintype "passive"))
      (node (ref "C12") (pin "2") (pinfunction "2_2") (pintype "passive"))
      (node (ref "C13") (pin "2") (pinfunction "2_2") (pintype "passive"))
      (node (ref "C14") (pin "2") (pinfunction "2_2") (pintype "passive"))
      (node (ref "C15") (pin "2") (pinfunction "2_2") (pintype "passive"))
      (node (ref "C16") (pin "2") (pinfunction "2_2") (pintype "passive"))
      (node (ref "C18") (pin "2") (pinfunction "2_2") (pintype "passive"))
      (node (ref "C20") (pin "2") (pinfunction "2_2") (pintype "passive"))
      (node (ref "C22") (pin "2") (pinfunction "2_2") (pintype "passive"))
      (node (ref "C23") (pin "2") (pinfunction "2_2") (pintype "passive"))
      (node (ref "C24") (pin "1") (pinfunction "1_1") (pintype "passive"))
      (node (ref "C25") (pin "1") (pinfunction "1_1") (pintype "passive"))
      (node (ref "C26") (pin "2") (pinfunction "2_2") (pintype "passive"))
      (node (ref "C3") (pin "-") (pinfunction "-_-") (pintype "passive"))
      (node (ref "C30") (pin "2") (pinfunction "2_2") (pintype "passive"))
      (node (ref "C33") (pin "2") (pinfunction "2_2") (pintype "passive"))
      (node (ref "C4") (pin "2") (pinfunction "2_2") (pintype "passive"))
      (node (ref "C5") (pin "2") (pinfunction "2_2") (pintype "passive"))
      (node (ref "C6") (pin "2") (pinfunction "2_2") (pintype "passive"))
      (node (ref "C7") (pin "2") (pinfunction "2_2") (pintype "passive"))
      (node (ref "C8") (pin "-") (pinfunction "-_-") (pintype "passive"))
      (node (ref "C9") (pin "-") (pinfunction "-_-") (pintype "passive"))
      (node (ref "IC1") (pin "1") (pinfunction "GND_1") (pintype "power_in"))
      (node (ref "IC2") (pin "2") (pinfunction "A_2") (pintype "passive"))
      (node (ref "IC3") (pin "1") (pinfunction "GND_1") (pintype "power_in"))
      (node (ref "IC4") (pin "8") (pinfunction "GND_8") (pintype "power_in"))
      (node (ref "IC5") (pin "3") (pinfunction "+IN_3") (pintype "input"))
      (node (ref "IC7") (pin "1") (pinfunction "C_1") (pintype "passive"))
      (node (ref "IC8") (pin "3") (pinfunction "+IN_3") (pintype "input"))
      (node (ref "IC8") (pin "4") (pinfunction "V-_4") (pintype "power_in"))
      (node (ref "IC8") (pin "5") (pinfunction "+IN_5") (pintype "input"))
      (node (ref "IC9") (pin "10") (pinfunction "+IN_10") (pintype "input"))
      (node (ref "IC9") (pin "11") (pinfunction "V-_11") (pintype "power_in"))
      (node (ref "IC9") (pin "12") (pinfunction "+IN_12") (pintype "input"))
      (node (ref "IC9") (pin "3") (pinfunction "+IN_3") (pintype "input"))
      (node (ref "IC9") (pin "5") (pinfunction "+IN_5") (pintype "input"))
      (node (ref "J1") (pin "P$3") (pinfunction "1_P$3") (pintype "passive"))
      (node (ref "J10") (pin "P$3") (pinfunction "1_P$3") (pintype "passive"))
      (node (ref "J11") (pin "P$3") (pinfunction "1_P$3") (pintype "passive"))
      (node (ref "J12") (pin "P$3") (pinfunction "1_P$3") (pintype "passive"))
      (node (ref "J13") (pin "P$3") (pinfunction "1_P$3") (pintype "passive"))
      (node (ref "J2") (pin "P$3") (pinfunction "1_P$3") (pintype "passive"))
      (node (ref "J3") (pin "P$3") (pinfunction "1_P$3") (pintype "passive"))
      (node (ref "J4") (pin "P$2") (pinfunction "3_P$2") (pintype "passive"))
      (node (ref "J4") (pin "P$3") (pinfunction "1_P$3") (pintype "passive"))
      (node (ref "J5") (pin "P$2") (pinfunction "3_P$2") (pintype "passive"))
      (node (ref "J5") (pin "P$3") (pinfunction "1_P$3") (pintype "passive"))
      (node (ref "J6") (pin "P$3") (pinfunction "1_P$3") (pintype "passive"))
      (node (ref "J7") (pin "P$3") (pinfunction "1_P$3") (pintype "passive"))
      (node (ref "J8") (pin "P$3") (pinfunction "1_P$3") (pintype "passive"))
      (node (ref "J9") (pin "P$2") (pinfunction "3_P$2") (pintype "passive"))
      (node (ref "J9") (pin "P$3") (pinfunction "1_P$3") (pintype "passive"))
      (node (ref "JP1") (pin "3") (pinfunction "3_3") (pintype "passive"))
      (node (ref "JP1") (pin "4") (pinfunction "4_4") (pintype "passive"))
      (node (ref "JP1") (pin "5") (pinfunction "5_5") (pintype "passive"))
      (node (ref "JP1") (pin "6") (pinfunction "6_6") (pintype "passive"))
      (node (ref "JP1") (pin "7") (pinfunction "7_7") (pintype "passive"))
      (node (ref "JP1") (pin "8") (pinfunction "8_8") (pintype "passive"))
      (node (ref "JP2") (pin "3") (pinfunction "3_3") (pintype "passive"))
      (node (ref "JP2") (pin "5") (pinfunction "5_5") (pintype "passive"))
      (node (ref "JP2") (pin "9") (pinfunction "9_9") (pintype "passive"))
      (node (ref "LED1") (pin "2") (pinfunction "C_2") (pintype "bidirectional"))
      (node (ref "LED2") (pin "2") (pinfunction "C_2") (pintype "bidirectional"))
      (node (ref "LED3") (pin "2") (pinfunction "C_2") (pintype "bidirectional"))
      (node (ref "Q1") (pin "GND") (pinfunction "GND_GND") (pintype "bidirectional"))
      (node (ref "Q2") (pin "E") (pinfunction "E_E") (pintype "passive"))
      (node (ref "Q3") (pin "E") (pinfunction "E_E") (pintype "passive"))
      (node (ref "Q4") (pin "E") (pinfunction "E_E") (pintype "passive"))
      (node (ref "Q5") (pin "E") (pinfunction "E_E") (pintype "passive"))
      (node (ref "Q6") (pin "E") (pinfunction "E_E") (pintype "passive"))
      (node (ref "R1") (pin "1") (pinfunction "1_1") (pintype "passive"))
      (node (ref "R17") (pin "P$3") (pinfunction "3_P$3") (pintype "passive"))
      (node (ref "R18") (pin "P$3") (pinfunction "3_P$3") (pintype "passive"))
      (node (ref "R19") (pin "P$3") (pinfunction "3_P$3") (pintype "passive"))
      (node (ref "R26") (pin "1") (pinfunction "1_1") (pintype "passive"))
      (node (ref "R50") (pin "1") (pinfunction "1_1") (pintype "passive"))
      (node (ref "R52") (pin "1") (pinfunction "1_1") (pintype "passive"))
      (node (ref "R6") (pin "P$3") (pinfunction "A_P$3") (pintype "passive"))
      (node (ref "R8") (pin "1") (pinfunction "1_1") (pintype "passive"))
      (node (ref "S1") (pin "1") (pinfunction "1_1") (pintype "passive"))
      (node (ref "S1") (pin "2") (pinfunction "2_2") (pintype "passive"))
      (node (ref "S2") (pin "1") (pinfunction "1_1") (pintype "passive"))
      (node (ref "S2") (pin "2") (pinfunction "2_2") (pintype "passive"))
      (node (ref "UC1") (pin "20") (pinfunction "PB2/BOOT1_20") (pintype "bidirectional"))
      (node (ref "UC1") (pin "23") (pinfunction "VSS_1_23") (pintype "power_in"))
      (node (ref "UC1") (pin "35") (pinfunction "VSS_2_35") (pintype "power_in"))
      (node (ref "UC1") (pin "47") (pinfunction "VSS_3_47") (pintype "power_in"))
      (node (ref "UC1") (pin "8") (pinfunction "VSS_A_8") (pintype "power_in"))
    )
    (net (code "19") (name "JTCK") (class "Default")
      (node (ref "JP2") (pin "4") (pinfunction "4_4") (pintype "passive"))
      (node (ref "UC1") (pin "37") (pinfunction "PA14/JTCK/SWCLK_37") (pintype "bidirectional"))
    )
    (net (code "20") (name "JTDI") (class "Default")
      (node (ref "JP2") (pin "8") (pinfunction "8_8") (pintype "passive"))
      (node (ref "UC1") (pin "38") (pinfunction "PA15/JTDI_38") (pintype "bidirectional"))
    )
    (net (code "21") (name "JTDO") (class "Default")
      (node (ref "JP2") (pin "6") (pinfunction "6_6") (pintype "passive"))
      (node (ref "UC1") (pin "39") (pinfunction "PB3/JTDO_39") (pintype "bidirectional"))
    )
    (net (code "22") (name "JTMS") (class "Default")
      (node (ref "JP2") (pin "2") (pinfunction "2_2") (pintype "passive"))
      (node (ref "UC1") (pin "34") (pinfunction "PA13/JTMS/SWDIO_34") (pintype "bidirectional"))
    )
    (net (code "23") (name "LEVEL_ADC") (class "Default")
      (node (ref "C34") (pin "2") (pinfunction "2_2") (pintype "passive"))
      (node (ref "IC9") (pin "7") (pinfunction "OUT_7") (pintype "output"))
      (node (ref "R45") (pin "1") (pinfunction "1_1") (pintype "passive"))
      (node (ref "UC1") (pin "16") (pinfunction "PA6/SPI1_MISO/ADC12_IN6/TIM3_CH1_16") (pintype "bidirectional"))
    )
    (net (code "24") (name "Net-(C19-Pad1)") (class "Default")
      (node (ref "C19") (pin "1") (pinfunction "1_1") (pintype "passive"))
      (node (ref "R13") (pin "1") (pinfunction "1_1") (pintype "passive"))
      (node (ref "R15") (pin "2") (pinfunction "2_2") (pintype "passive"))
    )
    (net (code "25") (name "Net-(C21-Pad1)") (class "Default")
      (node (ref "C21") (pin "1") (pinfunction "1_1") (pintype "passive"))
      (node (ref "R14") (pin "1") (pinfunction "1_1") (pintype "passive"))
      (node (ref "R16") (pin "2") (pinfunction "2_2") (pintype "passive"))
    )
    (net (code "26") (name "Net-(D1-PadA)") (class "Default")
      (node (ref "D1") (pin "A") (pinfunction "A_A") (pintype "passive"))
      (node (ref "JP1") (pin "1") (pinfunction "1_1") (pintype "passive"))
      (node (ref "JP1") (pin "2") (pinfunction "2_2") (pintype "passive"))
    )
    (net (code "27") (name "Net-(D2-PadC)") (class "Default")
      (node (ref "D2") (pin "C") (pinfunction "C_C") (pintype "passive"))
      (node (ref "JP1") (pin "10") (pinfunction "10_10") (pintype "passive"))
      (node (ref "JP1") (pin "9") (pinfunction "9_9") (pintype "passive"))
    )
    (net (code "28") (name "Net-(IC5A--IN)") (class "Default")
      (node (ref "IC5") (pin "2") (pinfunction "-IN_2") (pintype "input"))
      (node (ref "R20") (pin "1") (pinfunction "1_1") (pintype "passive"))
      (node (ref "R21") (pin "1") (pinfunction "1_1") (pintype "passive"))
      (node (ref "R23") (pin "2") (pinfunction "2_2") (pintype "passive"))
    )
    (net (code "29") (name "Net-(IC5A-OUT)") (class "Default")
      (node (ref "IC5") (pin "1") (pinfunction "OUT_1") (pintype "output"))
      (node (ref "R22") (pin "2") (pinfunction "2_2") (pintype "passive"))
      (node (ref "R23") (pin "1") (pinfunction "1_1") (pintype "passive"))
    )
    (net (code "30") (name "Net-(IC5B-+IN)") (class "Default")
      (node (ref "C22") (pin "1") (pinfunction "1_1") (pintype "passive"))
      (node (ref "IC5") (pin "5") (pinfunction "+IN_5") (pintype "input"))
      (node (ref "R15") (pin "1") (pinfunction "1_1") (pintype "passive"))
    )
    (net (code "31") (name "Net-(IC5B--IN)") (class "Default")
      (node (ref "C19") (pin "2") (pinfunction "2_2") (pintype "passive"))
      (node (ref "IC5") (pin "6") (pinfunction "-IN_6") (pintype "input"))
      (node (ref "IC5") (pin "7") (pinfunction "OUT_7") (pintype "output"))
      (node (ref "R20") (pin "2") (pinfunction "2_2") (pintype "passive"))
    )
    (net (code "32") (name "Net-(IC6A-+IN)") (class "Default")
      (node (ref "C21") (pin "2") (pinfunction "2_2") (pintype "passive"))
      (node (ref "IC6") (pin "3") (pinfunction "+IN_3") (pintype "input"))
      (node (ref "IC6") (pin "6") (pinfunction "-IN_6") (pintype "input"))
      (node (ref "IC6") (pin "7") (pinfunction "OUT_7") (pintype "output"))
    )
    (net (code "33") (name "Net-(IC6A--IN)") (class "Default")
      (node (ref "IC6") (pin "2") (pinfunction "-IN_2") (pintype "input"))
      (node (ref "R25") (pin "2") (pinfunction "2_2") (pintype "passive"))
      (node (ref "R26") (pin "2") (pinfunction "2_2") (pintype "passive"))
    )
    (net (code "34") (name "Net-(IC6A-OUT)") (class "Default")
      (node (ref "IC6") (pin "1") (pinfunction "OUT_1") (pintype "output"))
      (node (ref "R24") (pin "2") (pinfunction "2_2") (pintype "passive"))
      (node (ref "R25") (pin "1") (pinfunction "1_1") (pintype "passive"))
    )
    (net (code "35") (name "Net-(IC6B-+IN)") (class "Default")
      (node (ref "C23") (pin "1") (pinfunction "1_1") (pintype "passive"))
      (node (ref "IC6") (pin "5") (pinfunction "+IN_5") (pintype "input"))
      (node (ref "R16") (pin "1") (pinfunction "1_1") (pintype "passive"))
    )
    (net (code "36") (name "Net-(IC8A--IN)") (class "Default")
      (node (ref "C31") (pin "1") (pinfunction "1_1") (pintype "passive"))
      (node (ref "IC8") (pin "2") (pinfunction "-IN_2") (pintype "input"))
      (node (ref "R37") (pin "2") (pinfunction "2_2") (pintype "passive"))
      (node (ref "R38") (pin "1") (pinfunction "1_1") (pintype "passive"))
      (node (ref "R39") (pin "1") (pinfunction "1_1") (pintype "passive"))
    )
    (net (code "37") (name "Net-(IC8B--IN)") (class "Default")
      (node (ref "C27") (pin "1") (pinfunction "1_1") (pintype "passive"))
      (node (ref "IC8") (pin "6") (pinfunction "-IN_6") (pintype "input"))
      (node (ref "R34") (pin "2") (pinfunction "2_2") (pintype "passive"))
      (node (ref "R35") (pin "1") (pinfunction "1_1") (pintype "passive"))
      (node (ref "R36") (pin "1") (pinfunction "1_1") (pintype "passive"))
    )
    (net (code "38") (name "Net-(IC9A--IN)") (class "Default")
      (node (ref "C32") (pin "1") (pinfunction "1_1") (pintype "passive"))
      (node (ref "IC9") (pin "2") (pinfunction "-IN_2") (pintype "input"))
      (node (ref "R40") (pin "2") (pinfunction "2_2") (pintype "passive"))
      (node (ref "R41") (pin "1") (pinfunction "1_1") (pintype "passive"))
      (node (ref "R42") (pin "1") (pinfunction "1_1") (pintype "passive"))
    )
    (net (code "39") (name "Net-(IC9B--IN)") (class "Default")
      (node (ref "C34") (pin "1") (pinfunction "1_1") (pintype "passive"))
      (node (ref "IC9") (pin "6") (pinfunction "-IN_6") (pintype "input"))
      (node (ref "R43") (pin "1") (pinfunction "1_1") (pintype "passive"))
      (node (ref "R44") (pin "1") (pinfunction "1_1") (pintype "passive"))
      (node (ref "R45") (pin "2") (pinfunction "2_2") (pintype "passive"))
    )
    (net (code "40") (name "Net-(IC9C--IN)") (class "Default")
      (node (ref "C28") (pin "1") (pinfunction "1_1") (pintype "passive"))
      (node (ref "IC9") (pin "9") (pinfunction "-IN_9") (pintype "input"))
      (node (ref "R31") (pin "1") (pinfunction "1_1") (pintype "passive"))
      (node (ref "R32") (pin "1") (pinfunction "1_1") (pintype "passive"))
      (node (ref "R33") (pin "2") (pinfunction "2_2") (pintype "passive"))
    )
    (net (code "41") (name "Net-(IC9D--IN)") (class "Default")
      (node (ref "C29") (pin "1") (pinfunction "1_1") (pintype "passive"))
      (node (ref "IC9") (pin "13") (pinfunction "-IN_13") (pintype "input"))
      (node (ref "R28") (pin "2") (pinfunction "2_2") (pintype "passive"))
      (node (ref "R29") (pin "1") (pinfunction "1_1") (pintype "passive"))
      (node (ref "R30") (pin "1") (pinfunction "1_1") (pintype "passive"))
    )
    (net (code "42") (name "Net-(J1-2)") (class "Default")
      (node (ref "J1") (pin "P$1") (pinfunction "2_P$1") (pintype "passive"))
      (node (ref "R42") (pin "2") (pinfunction "2_2") (pintype "passive"))
    )
    (net (code "43") (name "Net-(J2-2)") (class "Default")
      (node (ref "J2") (pin "P$1") (pinfunction "2_P$1") (pintype "passive"))
      (node (ref "R29") (pin "2") (pinfunction "2_2") (pintype "passive"))
    )
    (net (code "44") (name "Net-(J3-2)") (class "Default")
      (node (ref "J3") (pin "P$1") (pinfunction "2_P$1") (pintype "passive"))
      (node (ref "R32") (pin "2") (pinfunction "2_2") (pintype "passive"))
    )
    (net (code "45") (name "Net-(J4-2)") (class "Default")
      (node (ref "J4") (pin "P$1") (pinfunction "2_P$1") (pintype "passive"))
      (node (ref "R55") (pin "1") (pinfunction "1_1") (pintype "passive"))
    )
    (net (code "46") (name "Net-(J5-2)") (class "Default")
      (node (ref "J5") (pin "P$1") (pinfunction "2_P$1") (pintype "passive"))
      (node (ref "R56") (pin "1") (pinfunction "1_1") (pintype "passive"))
    )
    (net (code "47") (name "Net-(J6-2)") (class "Default")
      (node (ref "J6") (pin "P$1") (pinfunction "2_P$1") (pintype "passive"))
      (node (ref "R39") (pin "2") (pinfunction "2_2") (pintype "passive"))
    )
    (net (code "48") (name "Net-(J7-2)") (class "Default")
      (node (ref "J7") (pin "P$1") (pinfunction "2_P$1") (pintype "passive"))
      (node (ref "R36") (pin "2") (pinfunction "2_2") (pintype "passive"))
    )
    (net (code "49") (name "Net-(J7-3)") (class "Default")
      (node (ref "J7") (pin "P$2") (pinfunction "3_P$2") (pintype "passive"))
      (node (ref "R46") (pin "1") (pinfunction "1_1") (pintype "passive"))
    )
    (net (code "50") (name "Net-(J8-2)") (class "Default")
      (node (ref "J8") (pin "P$1") (pinfunction "2_P$1") (pintype "passive"))
      (node (ref "R44") (pin "2") (pinfunction "2_2") (pintype "passive"))
    )
    (net (code "51") (name "Net-(J8-3)") (class "Default")
      (node (ref "J8") (pin "P$2") (pinfunction "3_P$2") (pintype "passive"))
      (node (ref "R60") (pin "2") (pinfunction "2_2") (pintype "passive"))
    )
    (net (code "52") (name "Net-(J9-2)") (class "Default")
      (node (ref "J9") (pin "P$1") (pinfunction "2_P$1") (pintype "passive"))
      (node (ref "R54") (pin "1") (pinfunction "1_1") (pintype "passive"))
    )
    (net (code "53") (name "Net-(J10-2)") (class "Default")
      (node (ref "J10") (pin "P$1") (pinfunction "2_P$1") (pintype "passive"))
      (node (ref "Q5") (pin "C") (pinfunction "C_C") (pintype "passive"))
      (node (ref "R50") (pin "2") (pinfunction "2_2") (pintype "passive"))
      (node (ref "R51") (pin "1") (pinfunction "1_1") (pintype "passive"))
    )
    (net (code "54") (name "Net-(J11-2)") (class "Default")
      (node (ref "J11") (pin "P$1") (pinfunction "2_P$1") (pintype "passive"))
      (node (ref "Q6") (pin "C") (pinfunction "C_C") (pintype "passive"))
      (node (ref "R52") (pin "2") (pinfunction "2_2") (pintype "passive"))
      (node (ref "R53") (pin "1") (pinfunction "1_1") (pintype "passive"))
    )
    (net (code "55") (name "Net-(J12-2)") (class "Default")
      (node (ref "J12") (pin "P$1") (pinfunction "2_P$1") (pintype "passive"))
      (node (ref "R24") (pin "1") (pinfunction "1_1") (pintype "passive"))
    )
    (net (code "56") (name "Net-(J13-2)") (class "Default")
      (node (ref "J13") (pin "P$1") (pinfunction "2_P$1") (pintype "passive"))
      (node (ref "R22") (pin "1") (pinfunction "1_1") (pintype "passive"))
    )
    (net (code "57") (name "Net-(LED1-GRN)") (class "Default")
      (node (ref "LED1") (pin "1") (pinfunction "GRN_1") (pintype "bidirectional"))
      (node (ref "R2") (pin "2") (pinfunction "2_2") (pintype "passive"))
    )
    (net (code "58") (name "Net-(LED1-RED)") (class "Default")
      (node (ref "LED1") (pin "3") (pinfunction "RED_3") (pintype "bidirectional"))
      (node (ref "R3") (pin "2") (pinfunction "2_2") (pintype "passive"))
    )
    (net (code "59") (name "Net-(LED2-GRN)") (class "Default")
      (node (ref "LED2") (pin "1") (pinfunction "GRN_1") (pintype "bidirectional"))
      (node (ref "R4") (pin "2") (pinfunction "2_2") (pintype "passive"))
    )
    (net (code "60") (name "Net-(LED2-RED)") (class "Default")
      (node (ref "LED2") (pin "3") (pinfunction "RED_3") (pintype "bidirectional"))
      (node (ref "R7") (pin "2") (pinfunction "2_2") (pintype "passive"))
    )
    (net (code "61") (name "Net-(LED3-GRN)") (class "Default")
      (node (ref "LED3") (pin "1") (pinfunction "GRN_1") (pintype "bidirectional"))
      (node (ref "R9") (pin "2") (pinfunction "2_2") (pintype "passive"))
    )
    (net (code "62") (name "Net-(LED3-RED)") (class "Default")
      (node (ref "LED3") (pin "3") (pinfunction "RED_3") (pintype "bidirectional"))
      (node (ref "R10") (pin "2") (pinfunction "2_2") (pintype "passive"))
    )
    (net (code "63") (name "Net-(Q2-PadB)") (class "Default")
      (node (ref "Q2") (pin "B") (pinfunction "B_B") (pintype "passive"))
      (node (ref "R55") (pin "2") (pinfunction "2_2") (pintype "passive"))
    )
    (net (code "64") (name "Net-(Q3-PadB)") (class "Default")
      (node (ref "Q3") (pin "B") (pinfunction "B_B") (pintype "passive"))
      (node (ref "R54") (pin "2") (pinfunction "2_2") (pintype "passive"))
    )
    (net (code "65") (name "Net-(Q4-PadB)") (class "Default")
      (node (ref "Q4") (pin "B") (pinfunction "B_B") (pintype "passive"))
      (node (ref "R56") (pin "2") (pinfunction "2_2") (pintype "passive"))
    )
    (net (code "66") (name "Net-(Q5-PadB)") (class "Default")
      (node (ref "Q5") (pin "B") (pinfunction "B_B") (pintype "passive"))
      (node (ref "R57") (pin "2") (pinfunction "2_2") (pintype "passive"))
    )
    (net (code "67") (name "Net-(Q6-PadB)") (class "Default")
      (node (ref "Q6") (pin "B") (pinfunction "B_B") (pintype "passive"))
      (node (ref "R58") (pin "2") (pinfunction "2_2") (pintype "passive"))
    )
    (net (code "68") (name "Net-(R5-E)") (class "Default")
      (node (ref "R5") (pin "P$1") (pinfunction "E_P$1") (pintype "passive"))
      (node (ref "R8") (pin "2") (pinfunction "2_2") (pintype "passive"))
    )
    (net (code "69") (name "Net-(R5-S)") (class "Default")
      (node (ref "R38") (pin "2") (pinfunction "2_2") (pintype "passive"))
      (node (ref "R5") (pin "P$2") (pinfunction "S_P$2") (pintype "passive"))
    )
    (net (code "70") (name "Net-(R17-2)") (class "Default")
      (node (ref "R17") (pin "P$2") (pinfunction "2_P$2") (pintype "passive"))
      (node (ref "R41") (pin "2") (pinfunction "2_2") (pintype "passive"))
    )
    (net (code "71") (name "Net-(R18-2)") (class "Default")
      (node (ref "R18") (pin "P$2") (pinfunction "2_P$2") (pintype "passive"))
      (node (ref "R30") (pin "2") (pinfunction "2_2") (pintype "passive"))
    )
    (net (code "72") (name "Net-(R19-2)") (class "Default")
      (node (ref "R19") (pin "P$2") (pinfunction "2_P$2") (pintype "passive"))
      (node (ref "R31") (pin "2") (pinfunction "2_2") (pintype "passive"))
    )
    (net (code "73") (name "Net-(R59-E)") (class "Default")
      (node (ref "R21") (pin "2") (pinfunction "2_2") (pintype "passive"))
      (node (ref "R59") (pin "1") (pinfunction "E_1") (pintype "passive"))
    )
    (net (code "74") (name "Net-(UC1-PB4{slash}NJTRST)") (class "Default")
      (node (ref "R2") (pin "1") (pinfunction "1_1") (pintype "passive"))
      (node (ref "UC1") (pin "40") (pinfunction "PB4/NJTRST_40") (pintype "bidirectional"))
    )
    (net (code "75") (name "Net-(UC1-PB5{slash}I2C1_SMBA)") (class "Default")
      (node (ref "R3") (pin "1") (pinfunction "1_1") (pintype "passive"))
      (node (ref "UC1") (pin "41") (pinfunction "PB5/I2C1_SMBA_41") (pintype "input"))
    )
    (net (code "76") (name "Net-(UC1-PB6{slash}I2C1_SCL{slash}TIM4_CH1)") (class "Default")
      (node (ref "R4") (pin "1") (pinfunction "1_1") (pintype "passive"))
      (node (ref "UC1") (pin "42") (pinfunction "PB6/I2C1_SCL/TIM4_CH1_42") (pintype "input"))
    )
    (net (code "77") (name "Net-(UC1-PB7{slash}I2C1_SDA{slash}TIM4_CH2)") (class "Default")
      (node (ref "R7") (pin "1") (pinfunction "1_1") (pintype "passive"))
      (node (ref "UC1") (pin "43") (pinfunction "PB7/I2C1_SDA/TIM4_CH2_43") (pintype "bidirectional"))
    )
    (net (code "78") (name "Net-(UC1-PB8{slash}TIM4_CH3)") (class "Default")
      (node (ref "R9") (pin "1") (pinfunction "1_1") (pintype "passive"))
      (node (ref "UC1") (pin "45") (pinfunction "PB8/TIM4_CH3_45") (pintype "bidirectional"))
    )
    (net (code "79") (name "Net-(UC1-PB9{slash}TIM4_CH4)") (class "Default")
      (node (ref "R10") (pin "1") (pinfunction "1_1") (pintype "passive"))
      (node (ref "UC1") (pin "46") (pinfunction "PB9/TIM4_CH4_46") (pintype "input"))
    )
    (net (code "80") (name "Net-(UC1-PD0-OSC_IN)") (class "Default")
      (node (ref "Q1") (pin "X1") (pinfunction "X1_X1") (pintype "bidirectional"))
      (node (ref "UC1") (pin "5") (pinfunction "PD0-OSC_IN_5") (pintype "input"))
    )
    (net (code "81") (name "Net-(UC1-PD1-OSC_OUT)") (class "Default")
      (node (ref "Q1") (pin "X2") (pinfunction "X2_X2") (pintype "bidirectional"))
      (node (ref "UC1") (pin "6") (pinfunction "PD1-OSC_OUT_6") (pintype "input"))
    )
    (net (code "82") (name "PROC_ADC") (class "Default")
      (node (ref "C28") (pin "2") (pinfunction "2_2") (pintype "passive"))
      (node (ref "IC9") (pin "8") (pinfunction "OUT_8") (pintype "output"))
      (node (ref "R33") (pin "1") (pinfunction "1_1") (pintype "passive"))
      (node (ref "UC1") (pin "17") (pinfunction "PA7/SPI1_MOSI/ADC12_IN7/TIM3_CH2_17") (pintype "bidirectional"))
    )
    (net (code "83") (name "RANGE_SW") (class "Default")
      (node (ref "S2") (pin "3") (pinfunction "3_3") (pintype "passive"))
      (node (ref "S2") (pin "4") (pinfunction "4_4") (pintype "passive"))
      (node (ref "UC1") (pin "11") (pinfunction "PA1/USART2_RTS/ADC12_IN1/TIM2_CH2_11") (pintype "bidirectional"))
    )
    (net (code "84") (name "RESET") (class "Default")
      (node (ref "JP2") (pin "10") (pinfunction "10_10") (pintype "passive"))
      (node (ref "R11") (pin "1") (pinfunction "1_1") (pintype "passive"))
      (node (ref "UC1") (pin "7") (pinfunction "NRST_7") (pintype "input"))
    )
    (net (code "85") (name "RX") (class "Default")
      (node (ref "UC1") (pin "31") (pinfunction "PA10/USART1_RX/TIM1_CH3_31") (pintype "bidirectional"))
    )
    (net (code "86") (name "SHAPE_ADC") (class "Default")
      (node (ref "C32") (pin "2") (pinfunction "2_2") (pintype "passive"))
      (node (ref "IC9") (pin "1") (pinfunction "OUT_1") (pintype "output"))
      (node (ref "R40") (pin "1") (pinfunction "1_1") (pintype "passive"))
      (node (ref "UC1") (pin "15") (pinfunction "PA5/SPI1_SCK/ADC12_IN5_15") (pintype "bidirectional"))
    )
    (net (code "87") (name "START") (class "Default")
      (node (ref "Q2") (pin "C") (pinfunction "C_C") (pintype "passive"))
      (node (ref "R47") (pin "1") (pinfunction "1_1") (pintype "passive"))
      (node (ref "UC1") (pin "22") (pinfunction "PB11/I2C2_SDA/USART3_RX_22") (pintype "input"))
    )
    (net (code "88") (name "TX") (class "Default")
      (node (ref "UC1") (pin "30") (pinfunction "PA9/USART1_TX/TIM1_CH2_30") (pintype "input"))
    )
    (net (code "89") (name "UNI") (class "Default")
      (node (ref "IC4") (pin "4") (pinfunction "OUTA_4") (pintype "output"))
      (node (ref "R14") (pin "2") (pinfunction "2_2") (pintype "passive"))
    )
    (net (code "90") (name "VCC") (class "Default")
      (node (ref "C18") (pin "1") (pinfunction "1_1") (pintype "passive"))
      (node (ref "C20") (pin "1") (pinfunction "1_1") (pintype "passive"))
      (node (ref "C3") (pin "+") (pinfunction "+_+") (pintype "passive"))
      (node (ref "C8") (pin "+") (pinfunction "+_+") (pintype "passive"))
      (node (ref "D1") (pin "C") (pinfunction "C_C") (pintype "passive"))
      (node (ref "IC1") (pin "3") (pinfunction "VIN_3") (pintype "input"))
      (node (ref "IC3") (pin "3") (pinfunction "VIN_3") (pintype "input"))
      (node (ref "IC5") (pin "8") (pinfunction "V+_8") (pintype "power_in"))
      (node (ref "IC6") (pin "8") (pinfunction "V+_8") (pintype "power_in"))
      (node (ref "R51") (pin "2") (pinfunction "2_2") (pintype "passive"))
      (node (ref "R53") (pin "2") (pinfunction "2_2") (pintype "passive"))
      (node (ref "R60") (pin "1") (pinfunction "1_1") (pintype "passive"))
    )
    (net (code "91") (name "VEE") (class "Default")
      (node (ref "C10") (pin "-") (pinfunction "-_-") (pintype "passive"))
      (node (ref "C24") (pin "2") (pinfunction "2_2") (pintype "passive"))
      (node (ref "C25") (pin "2") (pinfunction "2_2") (pintype "passive"))
      (node (ref "D2") (pin "A") (pinfunction "A_A") (pintype "passive"))
      (node (ref "IC5") (pin "4") (pinfunction "V-_4") (pintype "power_in"))
      (node (ref "IC6") (pin "4") (pinfunction "V-_4") (pintype "power_in"))
      (node (ref "R27") (pin "1") (pinfunction "1_1") (pintype "passive"))
    )
    (net (code "92") (name "VOCT_ADC") (class "Default")
      (node (ref "C31") (pin "2") (pinfunction "2_2") (pintype "passive"))
      (node (ref "IC8") (pin "1") (pinfunction "OUT_1") (pintype "output"))
      (node (ref "R37") (pin "1") (pinfunction "1_1") (pintype "passive"))
      (node (ref "UC1") (pin "13") (pinfunction "PA3/USART2_RX/ADC12_IN3/TIM2_CH4_13") (pintype "bidirectional"))
    )
    (net (code "93") (name "unconnected-(J1-3-PadP$2)") (class "Default")
      (node (ref "J1") (pin "P$2") (pinfunction "3_P$2") (pintype "passive"))
    )
    (net (code "94") (name "unconnected-(J2-3-PadP$2)") (class "Default")
      (node (ref "J2") (pin "P$2") (pinfunction "3_P$2") (pintype "passive"))
    )
    (net (code "95") (name "unconnected-(J3-3-PadP$2)") (class "Default")
      (node (ref "J3") (pin "P$2") (pinfunction "3_P$2") (pintype "passive"))
    )
    (net (code "96") (name "unconnected-(J6-3-PadP$2)") (class "Default")
      (node (ref "J6") (pin "P$2") (pinfunction "3_P$2") (pintype "passive"))
    )
    (net (code "97") (name "unconnected-(J10-3-PadP$2)") (class "Default")
      (node (ref "J10") (pin "P$2") (pinfunction "3_P$2") (pintype "passive"))
    )
    (net (code "98") (name "unconnected-(J11-3-PadP$2)") (class "Default")
      (node (ref "J11") (pin "P$2") (pinfunction "3_P$2") (pintype "passive"))
    )
    (net (code "99") (name "unconnected-(J12-3-PadP$2)") (class "Default")
      (node (ref "J12") (pin "P$2") (pinfunction "3_P$2") (pintype "passive"))
    )
    (net (code "100") (name "unconnected-(J13-3-PadP$2)") (class "Default")
      (node (ref "J13") (pin "P$2") (pinfunction "3_P$2") (pintype "passive"))
    )
    (net (code "101") (name "unconnected-(JP2-Pad7)") (class "Default")
      (node (ref "JP2") (pin "7") (pinfunction "7_7") (pintype "passive"))
    )
    (net (code "102") (name "unconnected-(UC1-PA8{slash}USART1_CK{slash}TIM1_CH1{slash}MCO-Pad29)") (class "Default")
      (node (ref "UC1") (pin "29") (pinfunction "PA8/USART1_CK/TIM1_CH1/MCO_29") (pintype "bidirectional"))
    )
    (net (code "103") (name "unconnected-(UC1-PB14{slash}SPI2_MISO{slash}USART3_RTS{slash}TIM1_CH2N-Pad27)") (class "Default")
      (node (ref "UC1") (pin "27") (pinfunction "PB14/SPI2_MISO/USART3_RTS/TIM1_CH2N_27") (pintype "input"))
    )
    (net (code "104") (name "unconnected-(UC1-PC13-TAMPER-RTC-Pad2)") (class "Default")
      (node (ref "UC1") (pin "2") (pinfunction "PC13-TAMPER-RTC_2") (pintype "input"))
    )
    (net (code "105") (name "unconnected-(UC1-PC14-OSC32_IN-Pad3)") (class "Default")
      (node (ref "UC1") (pin "3") (pinfunction "PC14-OSC32_IN_3") (pintype "input"))
    )
    (net (code "106") (name "unconnected-(UC1-PC15-OSC32_OUT-Pad4)") (class "Default")
      (node (ref "UC1") (pin "4") (pinfunction "PC15-OSC32_OUT_4") (pintype "input"))
    )
  )
)
